# ORingSW.net
KiCad netlist of a schematic drawn in Altium Designer
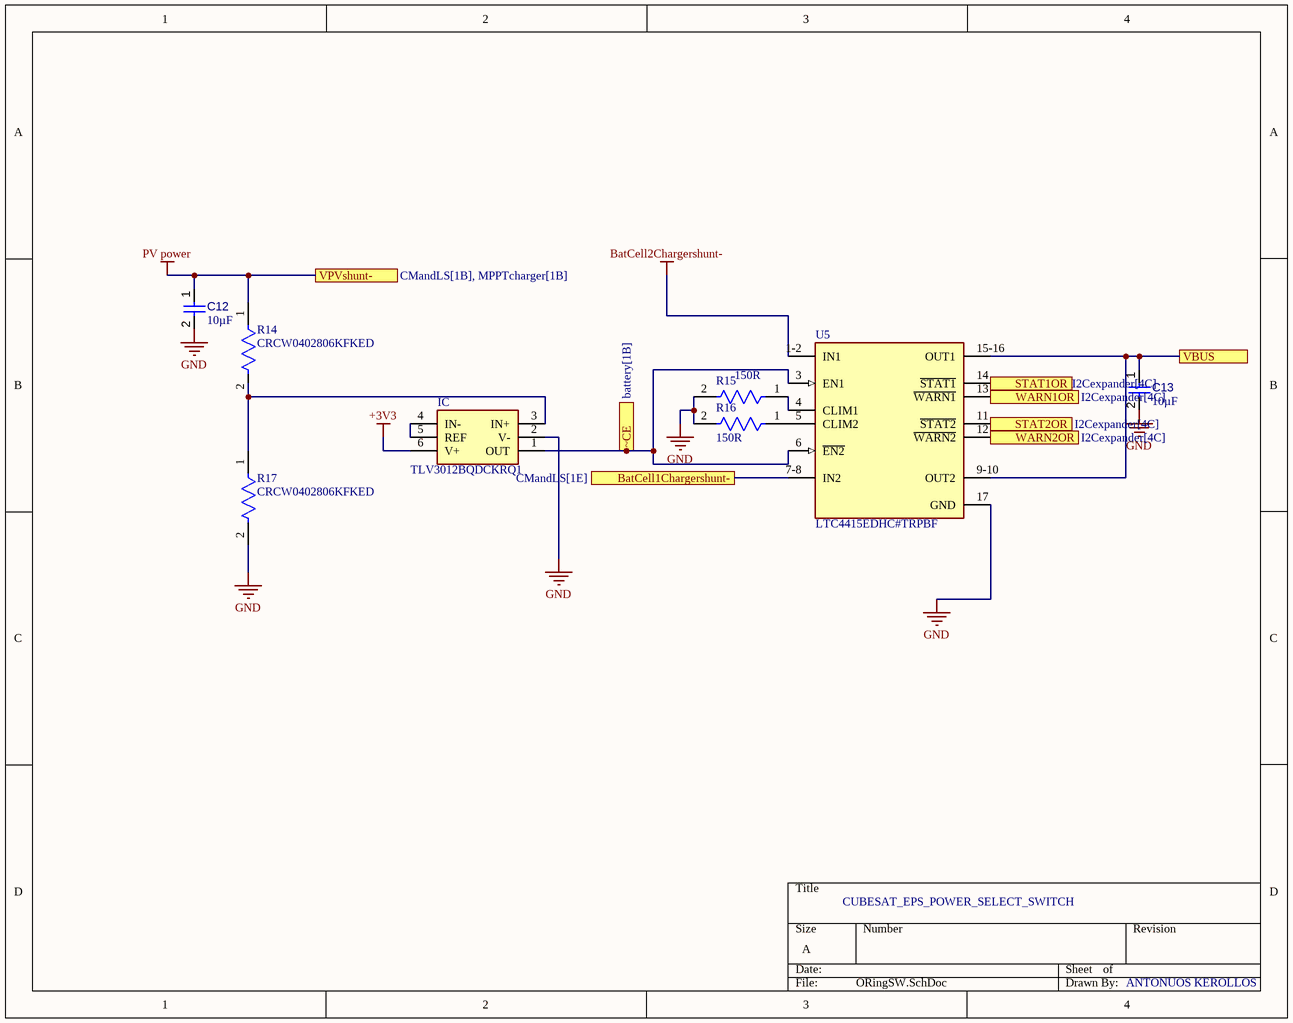
[diagram p0: ORingSW.SchDoc]

(export (version "E")
  (design (tool "Eeschema 10.0.6"))
  (components
    (comp (ref "C12")
      (value "10µF")
      (footprint "CAPC0402(1005)60_L")
      (description "Chip Capacitor, 10µF +/-40%, 6.3V, 0402, Thickness 0.6 mm")
      (fields (field (name "TOLERANCE") "10%") (field (name "Comment") "Capacitor 10µF +/-40% 6.3V 0402"))
      (libsource (lib "ANTONUOS KEROLLOS") (part "CAP-NP-2"))
    )
    (comp (ref "C13")
      (value "10µF")
      (footprint "CAPC0402(1005)60_L")
      (description "Chip Capacitor, 10µF +/-40%, 6.3V, 0402, Thickness 0.6 mm")
      (fields (field (name "TOLERANCE") "10%") (field (name "Comment") "Capacitor 10µF +/-40% 6.3V 0402"))
      (libsource (lib "ANTONUOS KEROLLOS") (part "CAP-NP-2"))
    )
    (comp (ref "IC")
      (value "TLV3012BQDCKRQ1")
      (footprint "SamacSys:SOT65P210X110-6N")
      (description "Integrated Circuit")
      (fields (field (name "MOUSER PART NUMBER") "595-TLV3012BQDCKRQ1"))
      (libsource (lib "*") (part "TLV3012BQDCKRQ1"))
    )
    (comp (ref "R14")
      (value "CRCW0402806KFKED")
      (footprint "FP-CRCW0402-e3-IPC_A")
      (description "RES Thick Film, 806kΩ, 1%, 0.063W, 100ppm/°C, 0402")
      (fields (field (name "TOLERANCE") "1%"))
      (libsource (lib "Altium Content Vault") (part "1029c3af85768c4190bb7ad29bc67b5"))
    )
    (comp (ref "R15")
      (value "150R")
      (footprint "FP-CRCW0402-e3-IPC_A")
      (description "RES Thick Film, 150Ω, 1%, 0.063W, 100ppm/°C, 0402")
      (fields (field (name "TOLERANCE") "1%"))
      (libsource (lib "Altium Content Vault") (part "1029c3af85768c4190bb7ad29bc67b5"))
    )
    (comp (ref "R16")
      (value "150R")
      (footprint "FP-CRCW0402-e3-IPC_A")
      (description "RES Thick Film, 150Ω, 1%, 0.063W, 100ppm/°C, 0402")
      (fields (field (name "TOLERANCE") "1%"))
      (libsource (lib "Altium Content Vault") (part "1029c3af85768c4190bb7ad29bc67b5"))
    )
    (comp (ref "R17")
      (value "CRCW0402806KFKED")
      (footprint "FP-CRCW0402-e3-IPC_A")
      (description "RES Thick Film, 806kΩ, 1%, 0.063W, 100ppm/°C, 0402")
      (fields (field (name "TOLERANCE") "1%"))
      (libsource (lib "Altium Content Vault") (part "1029c3af85768c4190bb7ad29bc67b5"))
    )
    (comp (ref "U5")
      (value "LTC4415EDHC#TRPBF")
      (footprint "FP-DHC-16-05-08-1872-A-MFG")
      (description "IC OR CTRLR SRC SELECT 16DFN")
      (libsource (lib "Altium Content Vault") (part "533f7461d30944814b8b3cb4b952162"))
    )
  )
  (nets
    (net (code "1") (name "+3V3") (class "Default")
      (node (ref "IC") (pin "6") (pinfunction "V+_6") (pintype "passive"))
    )
    (net (code "2") (name "/BatCell1Chargershunt-") (class "Default")
      (node (ref "U5") (pin "7-8") (pinfunction "IN2_7-8") (pintype "passive"))
    )
    (net (code "3") (name "/STAT1OR") (class "Default")
      (node (ref "U5") (pin "14") (pinfunction "~{STAT1}_14") (pintype "open_collector"))
    )
    (net (code "4") (name "/STAT2OR") (class "Default")
      (node (ref "U5") (pin "11") (pinfunction "~{STAT2}_11") (pintype "open_collector"))
    )
    (net (code "5") (name "/VBUS") (class "Default")
      (node (ref "C13") (pin "1") (pinfunction "1_1") (pintype "passive"))
      (node (ref "U5") (pin "15-16") (pinfunction "OUT1_15-16") (pintype "passive"))
      (node (ref "U5") (pin "9-10") (pinfunction "OUT2_9-10") (pintype "passive"))
    )
    (net (code "6") (name "/WARN1OR") (class "Default")
      (node (ref "U5") (pin "13") (pinfunction "~{WARN1}_13") (pintype "open_collector"))
    )
    (net (code "7") (name "/WARN2OR") (class "Default")
      (node (ref "U5") (pin "12") (pinfunction "~{WARN2}_12") (pintype "open_collector"))
    )
    (net (code "8") (name "/~CE") (class "Default")
      (node (ref "IC") (pin "1") (pinfunction "OUT_1") (pintype "passive"))
      (node (ref "U5") (pin "3") (pinfunction "EN1_3") (pintype "input"))
      (node (ref "U5") (pin "6") (pinfunction "~{EN2}_6") (pintype "input"))
    )
    (net (code "9") (name "BatCell2Chargershunt-") (class "Default")
      (node (ref "U5") (pin "1-2") (pinfunction "IN1_1-2") (pintype "passive"))
    )
    (net (code "10") (name "GND") (class "Default")
      (node (ref "C12") (pin "2") (pinfunction "2_2") (pintype "passive"))
      (node (ref "C13") (pin "2") (pinfunction "2_2") (pintype "passive"))
      (node (ref "IC") (pin "2") (pinfunction "V-_2") (pintype "passive"))
      (node (ref "R15") (pin "2") (pinfunction "2_2") (pintype "passive"))
      (node (ref "R16") (pin "2") (pinfunction "2_2") (pintype "passive"))
      (node (ref "R17") (pin "2") (pinfunction "2_2") (pintype "passive"))
      (node (ref "U5") (pin "17") (pinfunction "GND_17") (pintype "power_in"))
    )
    (net (code "11") (name "Net-(IC-IN+)") (class "Default")
      (node (ref "IC") (pin "3") (pinfunction "IN+_3") (pintype "passive"))
      (node (ref "R14") (pin "2") (pinfunction "2_2") (pintype "passive"))
      (node (ref "R17") (pin "1") (pinfunction "1_1") (pintype "passive"))
    )
    (net (code "12") (name "Net-(IC-IN-)") (class "Default")
      (node (ref "IC") (pin "4") (pinfunction "IN-_4") (pintype "passive"))
      (node (ref "IC") (pin "5") (pinfunction "REF_5") (pintype "passive"))
    )
    (net (code "13") (name "Net-(U5-CLIM1)") (class "Default")
      (node (ref "R15") (pin "1") (pinfunction "1_1") (pintype "passive"))
      (node (ref "U5") (pin "4") (pinfunction "CLIM1_4") (pintype "passive"))
    )
    (net (code "14") (name "Net-(U5-CLIM2)") (class "Default")
      (node (ref "R16") (pin "1") (pinfunction "1_1") (pintype "passive"))
      (node (ref "U5") (pin "5") (pinfunction "CLIM2_5") (pintype "passive"))
    )
    (net (code "15") (name "PV power") (class "Default")
      (node (ref "C12") (pin "1") (pinfunction "1_1") (pintype "passive"))
      (node (ref "R14") (pin "1") (pinfunction "1_1") (pintype "passive"))
    )
  )
)
